# OSCILLAR_HFB_V1p0_MIX.net
KiCad netlist of a schematic drawn in Altium Designer
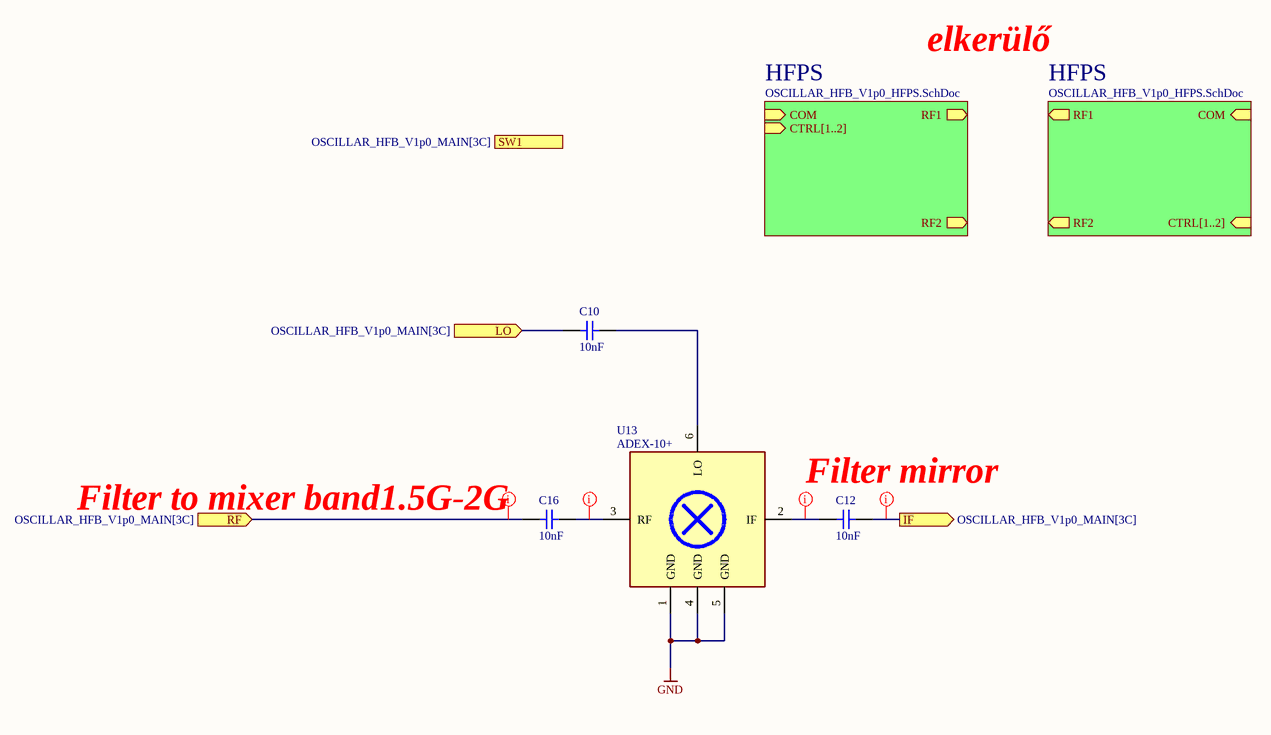
[diagram p0: OSCILLAR_HFB_V1p0_MIX.SchDoc]

(export (version "E")
  (design (tool "Eeschema 10.0.6"))
  (components
    (comp (ref "C10")
      (value "10nF")
      (footprint "CAP_0603")
      (description "MLCC capacitor")
      (libsource (lib "SCHLIB") (part "NP-CAPACITOR"))
    )
    (comp (ref "C12")
      (value "10nF")
      (footprint "CAP_0603")
      (description "MLCC capacitor")
      (libsource (lib "SCHLIB") (part "NP-CAPACITOR"))
    )
    (comp (ref "C16")
      (value "10nF")
      (footprint "CAP_0603")
      (description "MLCC capacitor")
      (libsource (lib "SCHLIB") (part "NP-CAPACITOR"))
    )
    (comp (ref "U13")
      (value "ADEX-10+")
      (footprint "CD542")
      (description "RF Mixer DBL BAL MIX, 10M-1GHz, +7dBm LO")
      (fields (field (name "PART NUMBER") "139-ADEX-10"))
      (libsource (lib "SCHLIB") (part "ADEX-10+"))
    )
  )
  (nets
    (net (code "5") (name "/IF") (class "Default")
      (node (ref "C12") (pin "1") (pinfunction "1_1") (pintype "passive"))
    )
    (net (code "6") (name "/LO") (class "Default")
      (node (ref "C10") (pin "2") (pinfunction "2_2") (pintype "passive"))
    )
    (net (code "7") (name "/RF") (class "Default")
      (node (ref "C16") (pin "2") (pinfunction "2_2") (pintype "passive"))
    )
    (net (code "13") (name "GND") (class "Default")
      (node (ref "U13") (pin "1") (pinfunction "GND_1") (pintype "passive"))
      (node (ref "U13") (pin "4") (pinfunction "GND_4") (pintype "passive"))
      (node (ref "U13") (pin "5") (pinfunction "GND_5") (pintype "passive"))
    )
    (net (code "14") (name "Net-(U13-IF)") (class "Default")
      (node (ref "C12") (pin "2") (pinfunction "2_2") (pintype "passive"))
      (node (ref "U13") (pin "2") (pinfunction "IF_2") (pintype "passive"))
    )
    (net (code "15") (name "Net-(U13-LO)") (class "Default")
      (node (ref "C10") (pin "1") (pinfunction "1_1") (pintype "passive"))
      (node (ref "U13") (pin "6") (pinfunction "LO_6") (pintype "passive"))
    )
    (net (code "16") (name "Net-(U13-RF)") (class "Default")
      (node (ref "C16") (pin "1") (pinfunction "1_1") (pintype "passive"))
      (node (ref "U13") (pin "3") (pinfunction "RF_3") (pintype "passive"))
    )
  )
)
